# Board4.net
KiCad netlist of a schematic drawn in EAGLE
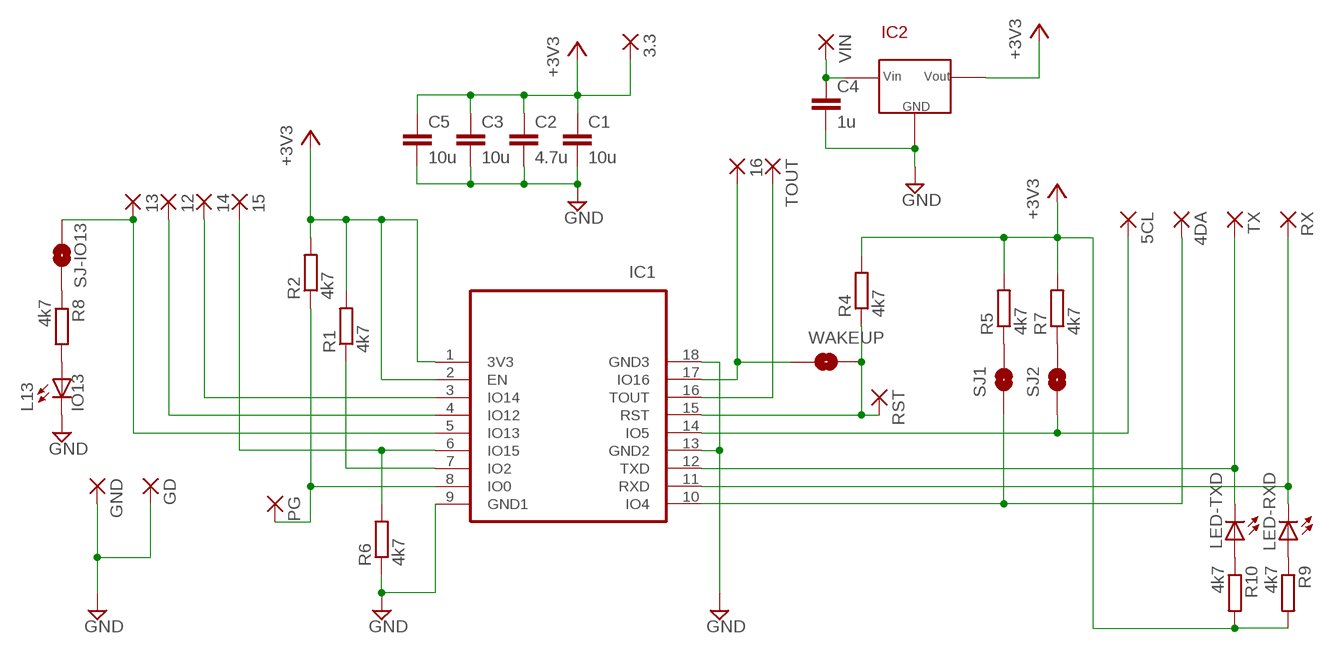
[diagram p0: schematic, sheet 1]

(export (version "E")
  (design (tool "Eeschema 10.0.6"))
  (components
    (comp (ref "3.3")
      (value "1,6/0,9")
      (footprint "eagle-import:1,6_0,9")
      (libsource (lib "eagle-import") (part "1,6/0,9"))
    )
    (comp (ref "4DA")
      (value "1,6/0,9")
      (footprint "eagle-import:1,6_0,9")
      (libsource (lib "eagle-import") (part "1,6/0,9"))
    )
    (comp (ref "5CL")
      (value "1,6/0,9")
      (footprint "eagle-import:1,6_0,9")
      (libsource (lib "eagle-import") (part "1,6/0,9"))
    )
    (comp (ref "12")
      (value "1,6/0,9")
      (footprint "eagle-import:1,6_0,9")
      (libsource (lib "eagle-import") (part "1,6/0,9"))
    )
    (comp (ref "13")
      (value "1,6/0,9")
      (footprint "eagle-import:1,6_0,9")
      (libsource (lib "eagle-import") (part "1,6/0,9"))
    )
    (comp (ref "14")
      (value "1,6/0,9")
      (footprint "eagle-import:1,6_0,9")
      (libsource (lib "eagle-import") (part "1,6/0,9"))
    )
    (comp (ref "15")
      (value "1,6/0,9")
      (footprint "eagle-import:1,6_0,9")
      (libsource (lib "eagle-import") (part "1,6/0,9"))
    )
    (comp (ref "16")
      (value "1,6/0,9")
      (footprint "eagle-import:1,6_0,9")
      (libsource (lib "eagle-import") (part "1,6/0,9"))
    )
    (comp (ref "C1")
      (value "10u")
      (footprint "eagle-import:C0805")
      (libsource (lib "eagle-import") (part "C-EUC0805"))
    )
    (comp (ref "C2")
      (value "4.7u")
      (footprint "eagle-import:C0805")
      (libsource (lib "eagle-import") (part "C-EUC0805"))
    )
    (comp (ref "C3")
      (value "10u")
      (footprint "eagle-import:C0805")
      (libsource (lib "eagle-import") (part "C-EUC0805"))
    )
    (comp (ref "C4")
      (value "1u")
      (footprint "eagle-import:C0603")
      (libsource (lib "eagle-import") (part "C-EUC0603"))
    )
    (comp (ref "C5")
      (value "10u")
      (footprint "eagle-import:C0805")
      (libsource (lib "eagle-import") (part "C-EUC0805"))
    )
    (comp (ref "GD")
      (value "1,6/0,9")
      (footprint "eagle-import:1,6_0,9")
      (libsource (lib "eagle-import") (part "1,6/0,9"))
    )
    (comp (ref "GND")
      (value "1,6/0,9")
      (footprint "eagle-import:1,6_0,9")
      (libsource (lib "eagle-import") (part "1,6/0,9"))
    )
    (comp (ref "IC1")
      (value "ESP-WROOM-02FRONT-FACE")
      (footprint "eagle-import:FRONT-FACE")
      (libsource (lib "eagle-import") (part "ESP-WROOM-02FRONT-FACE"))
    )
    (comp (ref "IC2")
      (value "NJM2845DL1")
      (footprint "eagle-import:TO-252-3")
      (libsource (lib "eagle-import") (part "NJM2845DL1"))
    )
    (comp (ref "L13")
      (value "IO13")
      (footprint "eagle-import:CHIP-LED0603")
      (libsource (lib "eagle-import") (part "LEDCHIP-LED0603"))
    )
    (comp (ref "LED-RXD")
      (value "R")
      (footprint "eagle-import:CHIP-LED0603")
      (libsource (lib "eagle-import") (part "LEDCHIP-LED0603"))
    )
    (comp (ref "LED-TXD")
      (value "T")
      (footprint "eagle-import:CHIP-LED0603")
      (libsource (lib "eagle-import") (part "LEDCHIP-LED0603"))
    )
    (comp (ref "PG")
      (value "1,6/0,9")
      (footprint "eagle-import:1,6_0,9")
      (libsource (lib "eagle-import") (part "1,6/0,9"))
    )
    (comp (ref "R1")
      (value "4k7")
      (footprint "eagle-import:R0603")
      (libsource (lib "eagle-import") (part "R-EU_R0603"))
    )
    (comp (ref "R2")
      (value "4k7")
      (footprint "eagle-import:R0603")
      (libsource (lib "eagle-import") (part "R-EU_R0603"))
    )
    (comp (ref "R4")
      (value "4k7")
      (footprint "eagle-import:R0603")
      (libsource (lib "eagle-import") (part "R-EU_R0603"))
    )
    (comp (ref "R5")
      (value "4k7")
      (footprint "eagle-import:R0603")
      (libsource (lib "eagle-import") (part "R-EU_R0603"))
    )
    (comp (ref "R6")
      (value "4k7")
      (footprint "eagle-import:R0603")
      (libsource (lib "eagle-import") (part "R-EU_R0603"))
    )
    (comp (ref "R7")
      (value "4k7")
      (footprint "eagle-import:R0603")
      (libsource (lib "eagle-import") (part "R-EU_R0603"))
    )
    (comp (ref "R8")
      (value "4k7")
      (footprint "eagle-import:R0603")
      (libsource (lib "eagle-import") (part "R-EU_R0603"))
    )
    (comp (ref "R9")
      (value "4k7")
      (footprint "eagle-import:R0603")
      (libsource (lib "eagle-import") (part "R-EU_R0603"))
    )
    (comp (ref "R10")
      (value "4k7")
      (footprint "eagle-import:R0603")
      (libsource (lib "eagle-import") (part "R-EU_R0603"))
    )
    (comp (ref "RST")
      (value "1,6/0,9")
      (footprint "eagle-import:1,6_0,9")
      (libsource (lib "eagle-import") (part "1,6/0,9"))
    )
    (comp (ref "RX")
      (value "1,6/0,9")
      (footprint "eagle-import:1,6_0,9")
      (libsource (lib "eagle-import") (part "1,6/0,9"))
    )
    (comp (ref "SJ-IO13")
      (value "SOLDERJUMPERNO")
      (footprint "eagle-import:SJ_2S-NO")
      (libsource (lib "eagle-import") (part "SOLDERJUMPERNO"))
    )
    (comp (ref "SJ1")
      (value "SDA/PU")
      (footprint "eagle-import:SJ_2S-NO")
      (libsource (lib "eagle-import") (part "SOLDERJUMPERNO"))
    )
    (comp (ref "SJ2")
      (value "SCL/PU")
      (footprint "eagle-import:SJ_2S-NO")
      (libsource (lib "eagle-import") (part "SOLDERJUMPERNO"))
    )
    (comp (ref "TOUT")
      (value "1,6/0,9")
      (footprint "eagle-import:1,6_0,9")
      (libsource (lib "eagle-import") (part "1,6/0,9"))
    )
    (comp (ref "TX")
      (value "1,6/0,9")
      (footprint "eagle-import:1,6_0,9")
      (libsource (lib "eagle-import") (part "1,6/0,9"))
    )
    (comp (ref "VIN")
      (value "1,6/0,9")
      (footprint "eagle-import:1,6_0,9")
      (libsource (lib "eagle-import") (part "1,6/0,9"))
    )
    (comp (ref "WAKEUP")
      (value "SOLDERJUMPERNO")
      (footprint "eagle-import:SJ_2S-NO")
      (libsource (lib "eagle-import") (part "SOLDERJUMPERNO"))
    )
  )
  (nets
    (net (code "1") (name "+3V3") (class "Default")
      (node (ref "3.3") (pin "1") (pinfunction "P_1") (pintype "passive"))
      (node (ref "C1") (pin "1") (pinfunction "1_1") (pintype "passive"))
      (node (ref "C2") (pin "1") (pinfunction "1_1") (pintype "passive"))
      (node (ref "C3") (pin "1") (pinfunction "1_1") (pintype "passive"))
      (node (ref "C5") (pin "1") (pinfunction "1_1") (pintype "passive"))
      (node (ref "IC1") (pin "1") (pinfunction "3V3_1") (pintype "power_in"))
      (node (ref "IC1") (pin "2") (pinfunction "EN_2") (pintype "bidirectional"))
      (node (ref "IC2") (pin "VOUT") (pinfunction "VOUT_VOUT") (pintype "power_in"))
      (node (ref "R1") (pin "2") (pinfunction "2_2") (pintype "passive"))
      (node (ref "R10") (pin "2") (pinfunction "2_2") (pintype "passive"))
      (node (ref "R2") (pin "2") (pinfunction "2_2") (pintype "passive"))
      (node (ref "R4") (pin "2") (pinfunction "2_2") (pintype "passive"))
      (node (ref "R5") (pin "2") (pinfunction "2_2") (pintype "passive"))
      (node (ref "R7") (pin "2") (pinfunction "2_2") (pintype "passive"))
      (node (ref "R9") (pin "2") (pinfunction "2_2") (pintype "passive"))
    )
    (net (code "2") (name "GND") (class "Default")
      (node (ref "C1") (pin "2") (pinfunction "2_2") (pintype "passive"))
      (node (ref "C2") (pin "2") (pinfunction "2_2") (pintype "passive"))
      (node (ref "C3") (pin "2") (pinfunction "2_2") (pintype "passive"))
      (node (ref "C4") (pin "2") (pinfunction "2_2") (pintype "passive"))
      (node (ref "C5") (pin "2") (pinfunction "2_2") (pintype "passive"))
      (node (ref "GD") (pin "1") (pinfunction "P_1") (pintype "passive"))
      (node (ref "GND") (pin "1") (pinfunction "P_1") (pintype "passive"))
      (node (ref "IC1") (pin "13") (pinfunction "GND2_13") (pintype "power_in"))
      (node (ref "IC1") (pin "18") (pinfunction "GND3_18") (pintype "power_in"))
      (node (ref "IC1") (pin "9") (pinfunction "GND1_9") (pintype "power_in"))
      (node (ref "IC2") (pin "GND") (pinfunction "GND_GND") (pintype "power_in"))
      (node (ref "L13") (pin "C") (pinfunction "C_C") (pintype "passive"))
      (node (ref "R6") (pin "1") (pinfunction "1_1") (pintype "passive"))
    )
    (net (code "3") (name "Net-(4DA-P)") (class "Default")
      (node (ref "4DA") (pin "1") (pinfunction "P_1") (pintype "passive"))
      (node (ref "IC1") (pin "10") (pinfunction "IO4_10") (pintype "bidirectional"))
      (node (ref "SJ1") (pin "1") (pinfunction "1_1") (pintype "passive"))
    )
    (net (code "4") (name "Net-(5CL-P)") (class "Default")
      (node (ref "5CL") (pin "1") (pinfunction "P_1") (pintype "passive"))
      (node (ref "IC1") (pin "14") (pinfunction "IO5_14") (pintype "open_collector"))
      (node (ref "SJ2") (pin "1") (pinfunction "1_1") (pintype "passive"))
    )
    (net (code "5") (name "Net-(12-P)") (class "Default")
      (node (ref "12") (pin "1") (pinfunction "P_1") (pintype "passive"))
      (node (ref "IC1") (pin "4") (pinfunction "IO12_4") (pintype "bidirectional"))
    )
    (net (code "6") (name "Net-(13-P)") (class "Default")
      (node (ref "13") (pin "1") (pinfunction "P_1") (pintype "passive"))
      (node (ref "IC1") (pin "5") (pinfunction "IO13_5") (pintype "bidirectional"))
      (node (ref "SJ-IO13") (pin "1") (pinfunction "1_1") (pintype "passive"))
    )
    (net (code "7") (name "Net-(14-P)") (class "Default")
      (node (ref "14") (pin "1") (pinfunction "P_1") (pintype "passive"))
      (node (ref "IC1") (pin "3") (pinfunction "IO14_3") (pintype "bidirectional"))
    )
    (net (code "8") (name "Net-(15-P)") (class "Default")
      (node (ref "15") (pin "1") (pinfunction "P_1") (pintype "passive"))
      (node (ref "IC1") (pin "6") (pinfunction "IO15_6") (pintype "bidirectional"))
      (node (ref "R6") (pin "2") (pinfunction "2_2") (pintype "passive"))
    )
    (net (code "9") (name "Net-(16-P)") (class "Default")
      (node (ref "16") (pin "1") (pinfunction "P_1") (pintype "passive"))
      (node (ref "IC1") (pin "17") (pinfunction "IO16_17") (pintype "bidirectional"))
      (node (ref "WAKEUP") (pin "1") (pinfunction "1_1") (pintype "passive"))
    )
    (net (code "10") (name "Net-(IC1-IO0)") (class "Default")
      (node (ref "IC1") (pin "8") (pinfunction "IO0_8") (pintype "bidirectional"))
      (node (ref "PG") (pin "1") (pinfunction "P_1") (pintype "passive"))
      (node (ref "R2") (pin "1") (pinfunction "1_1") (pintype "passive"))
    )
    (net (code "11") (name "Net-(IC1-IO2)") (class "Default")
      (node (ref "IC1") (pin "7") (pinfunction "IO2_7") (pintype "bidirectional"))
      (node (ref "R1") (pin "1") (pinfunction "1_1") (pintype "passive"))
    )
    (net (code "12") (name "Net-(IC1-RST)") (class "Default")
      (node (ref "IC1") (pin "15") (pinfunction "RST_15") (pintype "bidirectional"))
      (node (ref "R4") (pin "1") (pinfunction "1_1") (pintype "passive"))
      (node (ref "RST") (pin "1") (pinfunction "P_1") (pintype "passive"))
      (node (ref "WAKEUP") (pin "2") (pinfunction "2_2") (pintype "passive"))
    )
    (net (code "13") (name "Net-(IC1-RXD)") (class "Default")
      (node (ref "IC1") (pin "11") (pinfunction "RXD_11") (pintype "bidirectional"))
      (node (ref "LED-RXD") (pin "C") (pinfunction "C_C") (pintype "passive"))
      (node (ref "RX") (pin "1") (pinfunction "P_1") (pintype "passive"))
    )
    (net (code "14") (name "Net-(IC1-TOUT)") (class "Default")
      (node (ref "IC1") (pin "16") (pinfunction "TOUT_16") (pintype "bidirectional"))
      (node (ref "TOUT") (pin "1") (pinfunction "P_1") (pintype "passive"))
    )
    (net (code "15") (name "Net-(IC1-TXD)") (class "Default")
      (node (ref "IC1") (pin "12") (pinfunction "TXD_12") (pintype "bidirectional"))
      (node (ref "LED-TXD") (pin "C") (pinfunction "C_C") (pintype "passive"))
      (node (ref "TX") (pin "1") (pinfunction "P_1") (pintype "passive"))
    )
    (net (code "16") (name "Net-(L13-PadA)") (class "Default")
      (node (ref "L13") (pin "A") (pinfunction "A_A") (pintype "passive"))
      (node (ref "R8") (pin "2") (pinfunction "2_2") (pintype "passive"))
    )
    (net (code "17") (name "Net-(LED-RXD-PadA)") (class "Default")
      (node (ref "LED-RXD") (pin "A") (pinfunction "A_A") (pintype "passive"))
      (node (ref "R9") (pin "1") (pinfunction "1_1") (pintype "passive"))
    )
    (net (code "18") (name "Net-(LED-TXD-PadA)") (class "Default")
      (node (ref "LED-TXD") (pin "A") (pinfunction "A_A") (pintype "passive"))
      (node (ref "R10") (pin "1") (pinfunction "1_1") (pintype "passive"))
    )
    (net (code "19") (name "Net-(R5-Pad1)") (class "Default")
      (node (ref "R5") (pin "1") (pinfunction "1_1") (pintype "passive"))
      (node (ref "SJ1") (pin "2") (pinfunction "2_2") (pintype "passive"))
    )
    (net (code "20") (name "Net-(R7-Pad1)") (class "Default")
      (node (ref "R7") (pin "1") (pinfunction "1_1") (pintype "passive"))
      (node (ref "SJ2") (pin "2") (pinfunction "2_2") (pintype "passive"))
    )
    (net (code "21") (name "Net-(R8-Pad1)") (class "Default")
      (node (ref "R8") (pin "1") (pinfunction "1_1") (pintype "passive"))
      (node (ref "SJ-IO13") (pin "2") (pinfunction "2_2") (pintype "passive"))
    )
    (net (code "22") (name "Net-(VIN-P)") (class "Default")
      (node (ref "C4") (pin "1") (pinfunction "1_1") (pintype "passive"))
      (node (ref "IC2") (pin "VIN") (pinfunction "VIN_VIN") (pintype "power_in"))
      (node (ref "VIN") (pin "1") (pinfunction "P_1") (pintype "passive"))
    )
  )
)
